# USB_Tester_3_schematic.net
KiCad netlist of a schematic drawn in EAGLE
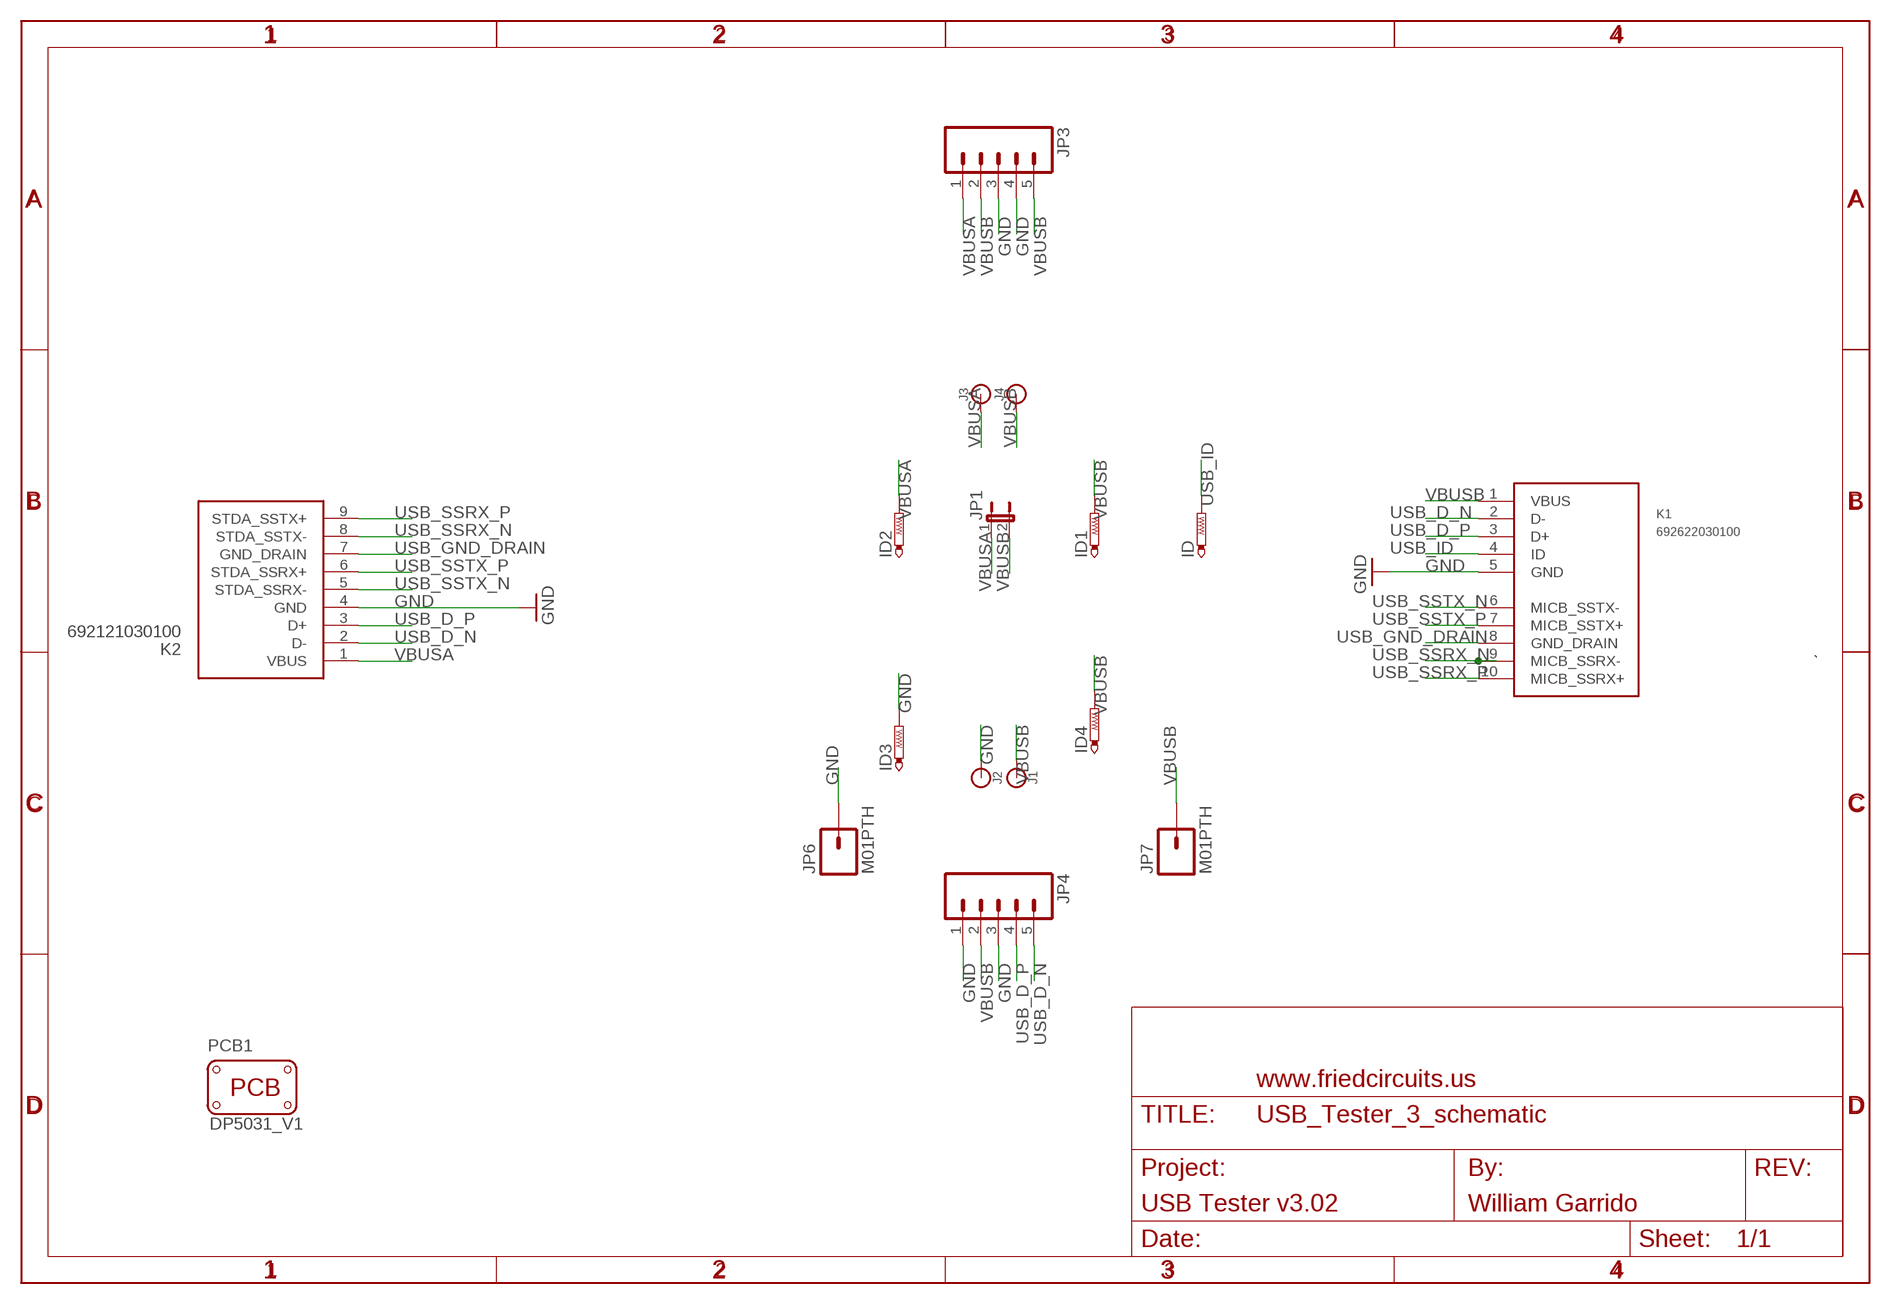
[diagram p0: schematic, sheet 1]

(export (version "E")
  (design (tool "Eeschema 10.0.6"))
  (components
    (comp (ref "ID")
      (value "PTR1PAD1-20")
      (footprint "eagle-import:P1-20")
      (libsource (lib "eagle-import") (part "PTR1PAD1-20"))
    )
    (comp (ref "ID1")
      (value "PTR1PAD1-20")
      (footprint "eagle-import:P1-20")
      (libsource (lib "eagle-import") (part "PTR1PAD1-20"))
    )
    (comp (ref "ID2")
      (value "PTR1PAD1-20")
      (footprint "eagle-import:P1-20")
      (libsource (lib "eagle-import") (part "PTR1PAD1-20"))
    )
    (comp (ref "ID3")
      (value "PTR1PAD1-20")
      (footprint "eagle-import:P1-20")
      (libsource (lib "eagle-import") (part "PTR1PAD1-20"))
    )
    (comp (ref "ID4")
      (value "PTR1PAD1-20")
      (footprint "eagle-import:P1-20")
      (libsource (lib "eagle-import") (part "PTR1PAD1-20"))
    )
    (comp (ref "J1")
      (value "BANANA_CONN")
      (footprint "eagle-import:BANANA_CONN")
      (libsource (lib "eagle-import") (part "BANANA_CONN"))
    )
    (comp (ref "J2")
      (value "BANANA_CONN")
      (footprint "eagle-import:BANANA_CONN")
      (libsource (lib "eagle-import") (part "BANANA_CONN"))
    )
    (comp (ref "J3")
      (value "BANANA_CONN")
      (footprint "eagle-import:BANANA_CONN")
      (libsource (lib "eagle-import") (part "BANANA_CONN"))
    )
    (comp (ref "J4")
      (value "BANANA_CONN")
      (footprint "eagle-import:BANANA_CONN")
      (libsource (lib "eagle-import") (part "BANANA_CONN"))
    )
    (comp (ref "JP1")
      (value "JUMPER-2PTH_LOCK")
      (footprint "eagle-import:1X02_LOCK")
      (libsource (lib "eagle-import") (part "JUMPER-2PTH_LOCK"))
    )
    (comp (ref "JP3")
      (value "M05LOCK")
      (footprint "eagle-import:1X05_LOCK")
      (libsource (lib "eagle-import") (part "M05LOCK"))
    )
    (comp (ref "JP4")
      (value "M05LOCK")
      (footprint "eagle-import:1X05_LOCK")
      (libsource (lib "eagle-import") (part "M05LOCK"))
    )
    (comp (ref "JP6")
      (value "M01PTH")
      (footprint "eagle-import:1X01")
      (libsource (lib "eagle-import") (part "M01PTH"))
    )
    (comp (ref "JP7")
      (value "M01PTH")
      (footprint "eagle-import:1X01")
      (libsource (lib "eagle-import") (part "M01PTH"))
    )
    (comp (ref "K1")
      (value "692622030100")
      (footprint "eagle-import:692622030100")
      (libsource (lib "eagle-import") (part "692622030100"))
    )
    (comp (ref "K2")
      (value "692121030100")
      (footprint "eagle-import:692121030100")
      (libsource (lib "eagle-import") (part "692121030100"))
    )
    (comp (ref "PCB1")
      (value "PCB_DP_RECTANGLE-31X50")
      (footprint "eagle-import:DP5031_V1")
      (libsource (lib "eagle-import") (part "PCB_DP_RECTANGLE-31X50"))
    )
    (comp (ref "U$1")
      (value "FRAME_DINA4_L")
      (footprint "eagle-import:FC_CREDIT")
      (fields
        (field (name "AUTHOR") "William Garrido")
        (field (name "FF3") "friedcircuits.us")
        (field (name "PROJECT") "USB Tester v3.02")
      )
      (libsource (lib "eagle-import") (part "FRAME_DINA4_L"))
    )
  )
  (nets
    (net (code "1") (name "/USB_D_N") (class "Default")
      (node (ref "JP4") (pin "5") (pinfunction "5_5") (pintype "passive"))
      (node (ref "K1") (pin "2") (pinfunction "D-_2") (pintype "bidirectional"))
      (node (ref "K2") (pin "2") (pinfunction "D-_2") (pintype "bidirectional"))
    )
    (net (code "2") (name "/USB_D_P") (class "Default")
      (node (ref "JP4") (pin "4") (pinfunction "4_4") (pintype "passive"))
      (node (ref "K1") (pin "3") (pinfunction "D+_3") (pintype "bidirectional"))
      (node (ref "K2") (pin "3") (pinfunction "D+_3") (pintype "bidirectional"))
    )
    (net (code "3") (name "/USB_GND_DRAIN") (class "Default")
      (node (ref "K1") (pin "8") (pinfunction "GND_DRAIN_8") (pintype "bidirectional"))
      (node (ref "K2") (pin "7") (pinfunction "GND_DRAIN_7") (pintype "bidirectional"))
    )
    (net (code "4") (name "/USB_ID") (class "Default")
      (node (ref "ID") (pin "TP") (pinfunction "TP_TP") (pintype "input"))
      (node (ref "K1") (pin "4") (pinfunction "ID_4") (pintype "bidirectional"))
    )
    (net (code "5") (name "/USB_SSRX_N") (class "Default")
      (node (ref "K1") (pin "9") (pinfunction "MICB_SSRX-_9") (pintype "bidirectional"))
      (node (ref "K2") (pin "8") (pinfunction "STDA_SSTX-_8") (pintype "bidirectional"))
    )
    (net (code "6") (name "/USB_SSRX_P") (class "Default")
      (node (ref "K1") (pin "10") (pinfunction "MICB_SSRX+_10") (pintype "bidirectional"))
      (node (ref "K2") (pin "9") (pinfunction "STDA_SSTX+_9") (pintype "bidirectional"))
    )
    (net (code "7") (name "/USB_SSTX_N") (class "Default")
      (node (ref "K1") (pin "6") (pinfunction "MICB_SSTX-_6") (pintype "bidirectional"))
      (node (ref "K2") (pin "5") (pinfunction "STDA_SSRX-_5") (pintype "bidirectional"))
    )
    (net (code "8") (name "/USB_SSTX_P") (class "Default")
      (node (ref "K1") (pin "7") (pinfunction "MICB_SSTX+_7") (pintype "bidirectional"))
      (node (ref "K2") (pin "6") (pinfunction "STDA_SSRX+_6") (pintype "bidirectional"))
    )
    (net (code "9") (name "/VBUSA") (class "Default")
      (node (ref "ID2") (pin "TP") (pinfunction "TP_TP") (pintype "input"))
      (node (ref "J3") (pin "P$1") (pinfunction "1_P$1") (pintype "passive"))
      (node (ref "JP1") (pin "1") (pinfunction "1_1") (pintype "passive"))
      (node (ref "JP3") (pin "1") (pinfunction "1_1") (pintype "passive"))
      (node (ref "K2") (pin "1") (pinfunction "VBUS_1") (pintype "bidirectional"))
    )
    (net (code "10") (name "/VBUSB") (class "Default")
      (node (ref "ID1") (pin "TP") (pinfunction "TP_TP") (pintype "input"))
      (node (ref "ID4") (pin "TP") (pinfunction "TP_TP") (pintype "input"))
      (node (ref "J1") (pin "P$1") (pinfunction "1_P$1") (pintype "passive"))
      (node (ref "J4") (pin "P$1") (pinfunction "1_P$1") (pintype "passive"))
      (node (ref "JP1") (pin "2") (pinfunction "2_2") (pintype "passive"))
      (node (ref "JP3") (pin "2") (pinfunction "2_2") (pintype "passive"))
      (node (ref "JP3") (pin "5") (pinfunction "5_5") (pintype "passive"))
      (node (ref "JP4") (pin "2") (pinfunction "2_2") (pintype "passive"))
      (node (ref "JP7") (pin "1") (pinfunction "1_1") (pintype "passive"))
      (node (ref "K1") (pin "1") (pinfunction "VBUS_1") (pintype "bidirectional"))
    )
    (net (code "11") (name "GND") (class "Default")
      (node (ref "ID3") (pin "TP") (pinfunction "TP_TP") (pintype "input"))
      (node (ref "J2") (pin "P$1") (pinfunction "1_P$1") (pintype "passive"))
      (node (ref "JP3") (pin "3") (pinfunction "3_3") (pintype "passive"))
      (node (ref "JP3") (pin "4") (pinfunction "4_4") (pintype "passive"))
      (node (ref "JP4") (pin "1") (pinfunction "1_1") (pintype "passive"))
      (node (ref "JP4") (pin "3") (pinfunction "3_3") (pintype "passive"))
      (node (ref "JP6") (pin "1") (pinfunction "1_1") (pintype "passive"))
      (node (ref "K1") (pin "5") (pinfunction "GND_5") (pintype "bidirectional"))
      (node (ref "K2") (pin "4") (pinfunction "GND_4") (pintype "bidirectional"))
    )
  )
)
